# PowerSupply.net
KiCad netlist of a schematic drawn in EAGLE
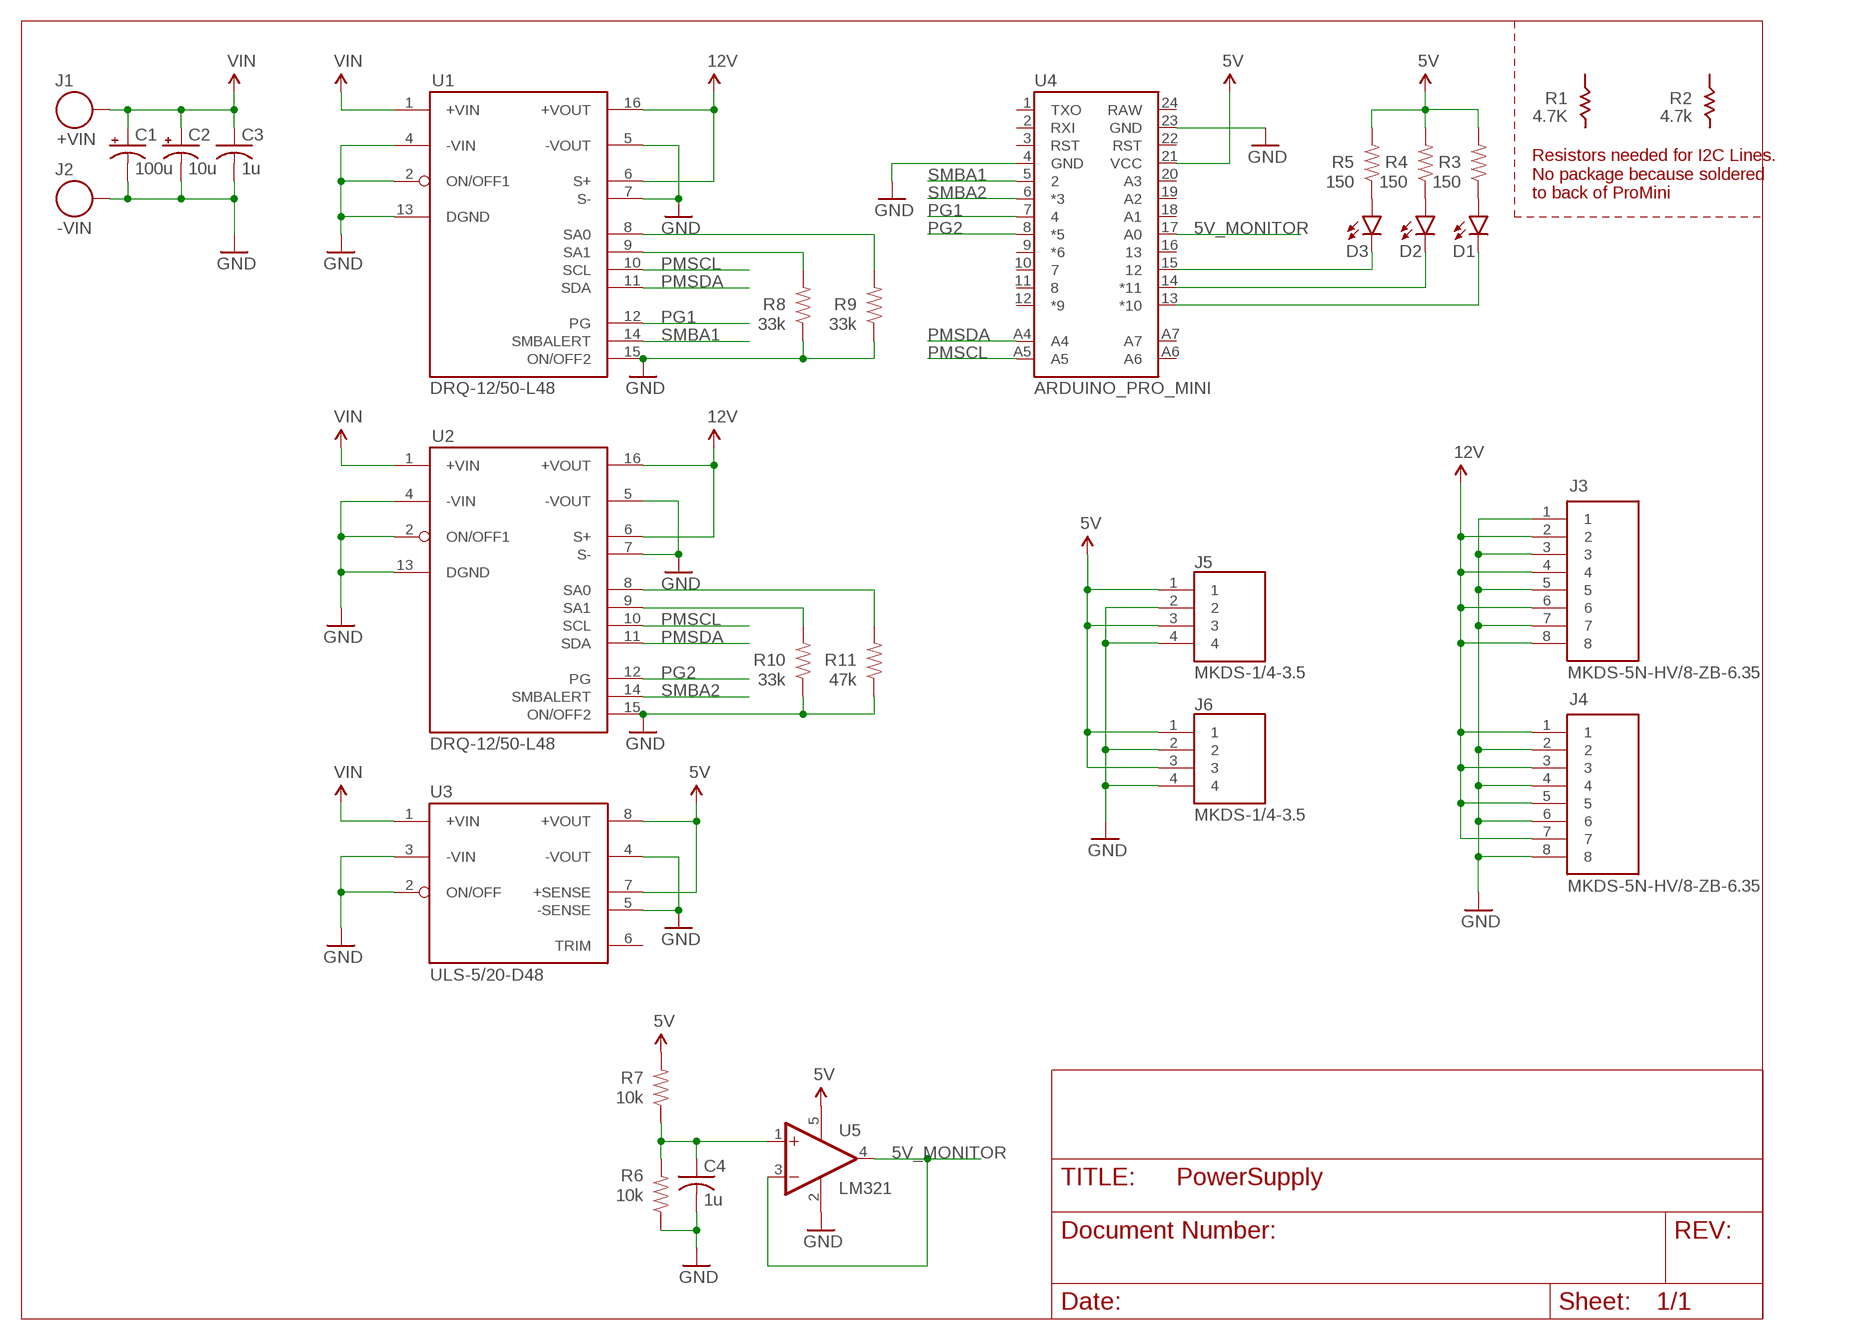
[diagram p0: schematic, sheet 1]

(export (version "E")
  (design (tool "Eeschema 10.0.6"))
  (components
    (comp (ref "C1")
      (value "100u")
      (footprint "eagle-import:PANASONIC_E")
      (libsource (lib "eagle-import") (part "CPOL-USE"))
    )
    (comp (ref "C2")
      (value "10u")
      (footprint "eagle-import:PANASONIC_D")
      (libsource (lib "eagle-import") (part "CPOL-USD"))
    )
    (comp (ref "C3")
      (value "1u")
      (footprint "eagle-import:C0603")
      (libsource (lib "eagle-import") (part "C-USC0603"))
    )
    (comp (ref "C4")
      (value "1u")
      (footprint "eagle-import:C0603")
      (libsource (lib "eagle-import") (part "C-USC0603"))
    )
    (comp (ref "D1")
      (value "LED1206")
      (footprint "eagle-import:LED-1206")
      (libsource (lib "eagle-import") (part "LED1206"))
    )
    (comp (ref "D2")
      (value "LED1206")
      (footprint "eagle-import:LED-1206")
      (libsource (lib "eagle-import") (part "LED1206"))
    )
    (comp (ref "D3")
      (value "LED1206")
      (footprint "eagle-import:LED-1206")
      (libsource (lib "eagle-import") (part "LED1206"))
    )
    (comp (ref "J1")
      (value "+VIN")
      (footprint "eagle-import:10AWG")
      (libsource (lib "eagle-import") (part "SINGLE_PIN"))
    )
    (comp (ref "J2")
      (value "-VIN")
      (footprint "eagle-import:10AWG")
      (libsource (lib "eagle-import") (part "SINGLE_PIN"))
    )
    (comp (ref "J3")
      (value "MKDS-5N-HV/8-ZB-6.35")
      (footprint "eagle-import:1777600")
      (libsource (lib "eagle-import") (part "MKDS-5N-HV/8-ZB-6.35"))
    )
    (comp (ref "J4")
      (value "MKDS-5N-HV/8-ZB-6.35")
      (footprint "eagle-import:1777600")
      (libsource (lib "eagle-import") (part "MKDS-5N-HV/8-ZB-6.35"))
    )
    (comp (ref "J5")
      (value "MKDS-1/4-3.5")
      (footprint "eagle-import:1751264")
      (libsource (lib "eagle-import") (part "MKDS-1/4-3.5"))
    )
    (comp (ref "J6")
      (value "MKDS-1/4-3.5")
      (footprint "eagle-import:1751264")
      (libsource (lib "eagle-import") (part "MKDS-1/4-3.5"))
    )
    (comp (ref "R3")
      (value "150")
      (footprint "eagle-import:0603-RES")
      (libsource (lib "eagle-import") (part "RESISTOR0603-RES"))
    )
    (comp (ref "R4")
      (value "150")
      (footprint "eagle-import:0603-RES")
      (libsource (lib "eagle-import") (part "RESISTOR0603-RES"))
    )
    (comp (ref "R5")
      (value "150")
      (footprint "eagle-import:0603-RES")
      (libsource (lib "eagle-import") (part "RESISTOR0603-RES"))
    )
    (comp (ref "R6")
      (value "10k")
      (footprint "eagle-import:0603-RES")
      (libsource (lib "eagle-import") (part "RESISTOR0603-RES"))
    )
    (comp (ref "R7")
      (value "10k")
      (footprint "eagle-import:0603-RES")
      (libsource (lib "eagle-import") (part "RESISTOR0603-RES"))
    )
    (comp (ref "R8")
      (value "33k")
      (footprint "eagle-import:0603-RES")
      (libsource (lib "eagle-import") (part "RESISTOR0603-RES"))
    )
    (comp (ref "R9")
      (value "33k")
      (footprint "eagle-import:0603-RES")
      (libsource (lib "eagle-import") (part "RESISTOR0603-RES"))
    )
    (comp (ref "R10")
      (value "33k")
      (footprint "eagle-import:0603-RES")
      (libsource (lib "eagle-import") (part "RESISTOR0603-RES"))
    )
    (comp (ref "R11")
      (value "47k")
      (footprint "eagle-import:0603-RES")
      (libsource (lib "eagle-import") (part "RESISTOR0603-RES"))
    )
    (comp (ref "U1")
      (value "DRQ-12/50-L48")
      (footprint "eagle-import:ABC(PMBUS)")
      (libsource (lib "eagle-import") (part "DRQ-12/50-L48"))
    )
    (comp (ref "U2")
      (value "DRQ-12/50-L48")
      (footprint "eagle-import:ABC(PMBUS)")
      (libsource (lib "eagle-import") (part "DRQ-12/50-L48"))
    )
    (comp (ref "U3")
      (value "ULS-5/20-D48")
      (footprint "eagle-import:1_16_BRICK_THROUGH_HOLE")
      (libsource (lib "eagle-import") (part "ULS-5/20-D48"))
    )
    (comp (ref "U4")
      (value "ARDUINO_PRO_MINI")
      (footprint "eagle-import:ARDUINO_PRO_MINI")
      (libsource (lib "eagle-import") (part "ARDUINO_PRO_MINI"))
    )
    (comp (ref "U5")
      (value "LM321")
      (footprint "eagle-import:SOT23-5")
      (libsource (lib "eagle-import") (part "LM321?MF"))
    )
  )
  (nets
    (net (code "1") (name "/5V_MONITOR") (class "Default")
      (node (ref "U4") (pin "17") (pinfunction "A0_17") (pintype "bidirectional"))
      (node (ref "U5") (pin "3") (pinfunction "-IN_3") (pintype "input"))
      (node (ref "U5") (pin "4") (pinfunction "OUT_4") (pintype "output"))
    )
    (net (code "2") (name "/PG1") (class "Default")
      (node (ref "U1") (pin "12") (pinfunction "PG_12") (pintype "bidirectional"))
      (node (ref "U4") (pin "7") (pinfunction "4_7") (pintype "bidirectional"))
    )
    (net (code "3") (name "/PG2") (class "Default")
      (node (ref "U2") (pin "12") (pinfunction "PG_12") (pintype "bidirectional"))
      (node (ref "U4") (pin "8") (pinfunction "*5_8") (pintype "bidirectional"))
    )
    (net (code "4") (name "/PMSCL") (class "Default")
      (node (ref "U1") (pin "10") (pinfunction "SCL_10") (pintype "bidirectional"))
      (node (ref "U2") (pin "10") (pinfunction "SCL_10") (pintype "bidirectional"))
      (node (ref "U4") (pin "A5") (pinfunction "A5_A5") (pintype "bidirectional"))
    )
    (net (code "5") (name "/PMSDA") (class "Default")
      (node (ref "U1") (pin "11") (pinfunction "SDA_11") (pintype "bidirectional"))
      (node (ref "U2") (pin "11") (pinfunction "SDA_11") (pintype "bidirectional"))
      (node (ref "U4") (pin "A4") (pinfunction "A4_A4") (pintype "bidirectional"))
    )
    (net (code "6") (name "/SMBA1") (class "Default")
      (node (ref "U1") (pin "14") (pinfunction "SMBALERT_14") (pintype "bidirectional"))
      (node (ref "U4") (pin "5") (pinfunction "2_5") (pintype "bidirectional"))
    )
    (net (code "7") (name "/SMBA2") (class "Default")
      (node (ref "U2") (pin "14") (pinfunction "SMBALERT_14") (pintype "bidirectional"))
      (node (ref "U4") (pin "6") (pinfunction "*3_6") (pintype "bidirectional"))
    )
    (net (code "8") (name "5V") (class "Default")
      (node (ref "J5") (pin "1") (pinfunction "1_1") (pintype "bidirectional"))
      (node (ref "J5") (pin "3") (pinfunction "3_3") (pintype "bidirectional"))
      (node (ref "J6") (pin "1") (pinfunction "1_1") (pintype "bidirectional"))
      (node (ref "J6") (pin "3") (pinfunction "3_3") (pintype "bidirectional"))
      (node (ref "R3") (pin "2") (pinfunction "2_2") (pintype "passive"))
      (node (ref "R4") (pin "2") (pinfunction "2_2") (pintype "passive"))
      (node (ref "R5") (pin "2") (pinfunction "2_2") (pintype "passive"))
      (node (ref "R7") (pin "2") (pinfunction "2_2") (pintype "passive"))
      (node (ref "U3") (pin "7") (pinfunction "+SENSE_7") (pintype "bidirectional"))
      (node (ref "U3") (pin "8") (pinfunction "+VOUT_8") (pintype "bidirectional"))
      (node (ref "U4") (pin "21") (pinfunction "VCC_21") (pintype "bidirectional"))
      (node (ref "U5") (pin "5") (pinfunction "V+_5") (pintype "power_in"))
    )
    (net (code "9") (name "12V") (class "Default")
      (node (ref "J3") (pin "2") (pinfunction "2_2") (pintype "bidirectional"))
      (node (ref "J3") (pin "4") (pinfunction "4_4") (pintype "bidirectional"))
      (node (ref "J3") (pin "6") (pinfunction "6_6") (pintype "bidirectional"))
      (node (ref "J3") (pin "8") (pinfunction "8_8") (pintype "bidirectional"))
      (node (ref "J4") (pin "1") (pinfunction "1_1") (pintype "bidirectional"))
      (node (ref "J4") (pin "3") (pinfunction "3_3") (pintype "bidirectional"))
      (node (ref "J4") (pin "5") (pinfunction "5_5") (pintype "bidirectional"))
      (node (ref "J4") (pin "7") (pinfunction "7_7") (pintype "bidirectional"))
      (node (ref "U1") (pin "16") (pinfunction "+VOUT_16") (pintype "bidirectional"))
      (node (ref "U1") (pin "6") (pinfunction "S+_6") (pintype "bidirectional"))
      (node (ref "U2") (pin "16") (pinfunction "+VOUT_16") (pintype "bidirectional"))
      (node (ref "U2") (pin "6") (pinfunction "S+_6") (pintype "bidirectional"))
    )
    (net (code "10") (name "GND") (class "Default")
      (node (ref "C1") (pin "-") (pinfunction "-_-") (pintype "passive"))
      (node (ref "C2") (pin "-") (pinfunction "-_-") (pintype "passive"))
      (node (ref "C3") (pin "2") (pinfunction "2_2") (pintype "passive"))
      (node (ref "C4") (pin "2") (pinfunction "2_2") (pintype "passive"))
      (node (ref "J2") (pin "P$1") (pinfunction "P$1_P$1") (pintype "bidirectional"))
      (node (ref "J3") (pin "1") (pinfunction "1_1") (pintype "bidirectional"))
      (node (ref "J3") (pin "3") (pinfunction "3_3") (pintype "bidirectional"))
      (node (ref "J3") (pin "5") (pinfunction "5_5") (pintype "bidirectional"))
      (node (ref "J3") (pin "7") (pinfunction "7_7") (pintype "bidirectional"))
      (node (ref "J4") (pin "2") (pinfunction "2_2") (pintype "bidirectional"))
      (node (ref "J4") (pin "4") (pinfunction "4_4") (pintype "bidirectional"))
      (node (ref "J4") (pin "6") (pinfunction "6_6") (pintype "bidirectional"))
      (node (ref "J4") (pin "8") (pinfunction "8_8") (pintype "bidirectional"))
      (node (ref "J5") (pin "2") (pinfunction "2_2") (pintype "bidirectional"))
      (node (ref "J5") (pin "4") (pinfunction "4_4") (pintype "bidirectional"))
      (node (ref "J6") (pin "2") (pinfunction "2_2") (pintype "bidirectional"))
      (node (ref "J6") (pin "4") (pinfunction "4_4") (pintype "bidirectional"))
      (node (ref "R10") (pin "1") (pinfunction "1_1") (pintype "passive"))
      (node (ref "R11") (pin "1") (pinfunction "1_1") (pintype "passive"))
      (node (ref "R6") (pin "1") (pinfunction "1_1") (pintype "passive"))
      (node (ref "R8") (pin "1") (pinfunction "1_1") (pintype "passive"))
      (node (ref "R9") (pin "1") (pinfunction "1_1") (pintype "passive"))
      (node (ref "U1") (pin "13") (pinfunction "DGND_13") (pintype "bidirectional"))
      (node (ref "U1") (pin "15") (pinfunction "ON/OFF2_15") (pintype "bidirectional"))
      (node (ref "U1") (pin "2") (pinfunction "ON/OFF1_2") (pintype "bidirectional"))
      (node (ref "U1") (pin "4") (pinfunction "-VIN_4") (pintype "bidirectional"))
      (node (ref "U1") (pin "5") (pinfunction "-VOUT_5") (pintype "bidirectional"))
      (node (ref "U1") (pin "7") (pinfunction "S-_7") (pintype "bidirectional"))
      (node (ref "U2") (pin "13") (pinfunction "DGND_13") (pintype "bidirectional"))
      (node (ref "U2") (pin "15") (pinfunction "ON/OFF2_15") (pintype "bidirectional"))
      (node (ref "U2") (pin "2") (pinfunction "ON/OFF1_2") (pintype "bidirectional"))
      (node (ref "U2") (pin "4") (pinfunction "-VIN_4") (pintype "bidirectional"))
      (node (ref "U2") (pin "5") (pinfunction "-VOUT_5") (pintype "bidirectional"))
      (node (ref "U2") (pin "7") (pinfunction "S-_7") (pintype "bidirectional"))
      (node (ref "U3") (pin "2") (pinfunction "ON/OFF_2") (pintype "bidirectional"))
      (node (ref "U3") (pin "3") (pinfunction "-VIN_3") (pintype "bidirectional"))
      (node (ref "U3") (pin "4") (pinfunction "-VOUT_4") (pintype "bidirectional"))
      (node (ref "U3") (pin "5") (pinfunction "-SENSE_5") (pintype "bidirectional"))
      (node (ref "U4") (pin "23") (pinfunction "GND_23") (pintype "bidirectional"))
      (node (ref "U4") (pin "4") (pinfunction "GND_4") (pintype "bidirectional"))
      (node (ref "U5") (pin "2") (pinfunction "V-_2") (pintype "power_in"))
    )
    (net (code "11") (name "Net-(D1-PadA)") (class "Default")
      (node (ref "D1") (pin "A") (pinfunction "A_A") (pintype "passive"))
      (node (ref "R3") (pin "1") (pinfunction "1_1") (pintype "passive"))
    )
    (net (code "12") (name "Net-(D2-PadA)") (class "Default")
      (node (ref "D2") (pin "A") (pinfunction "A_A") (pintype "passive"))
      (node (ref "R4") (pin "1") (pinfunction "1_1") (pintype "passive"))
    )
    (net (code "13") (name "Net-(D3-PadA)") (class "Default")
      (node (ref "D3") (pin "A") (pinfunction "A_A") (pintype "passive"))
      (node (ref "R5") (pin "1") (pinfunction "1_1") (pintype "passive"))
    )
    (net (code "14") (name "Net-(U1-SA0)") (class "Default")
      (node (ref "R9") (pin "2") (pinfunction "2_2") (pintype "passive"))
      (node (ref "U1") (pin "8") (pinfunction "SA0_8") (pintype "bidirectional"))
    )
    (net (code "15") (name "Net-(U1-SA1)") (class "Default")
      (node (ref "R8") (pin "2") (pinfunction "2_2") (pintype "passive"))
      (node (ref "U1") (pin "9") (pinfunction "SA1_9") (pintype "bidirectional"))
    )
    (net (code "16") (name "Net-(U2-SA0)") (class "Default")
      (node (ref "R11") (pin "2") (pinfunction "2_2") (pintype "passive"))
      (node (ref "U2") (pin "8") (pinfunction "SA0_8") (pintype "bidirectional"))
    )
    (net (code "17") (name "Net-(U2-SA1)") (class "Default")
      (node (ref "R10") (pin "2") (pinfunction "2_2") (pintype "passive"))
      (node (ref "U2") (pin "9") (pinfunction "SA1_9") (pintype "bidirectional"))
    )
    (net (code "18") (name "Net-(U4-*10)") (class "Default")
      (node (ref "D1") (pin "C") (pinfunction "C_C") (pintype "passive"))
      (node (ref "U4") (pin "13") (pinfunction "*10_13") (pintype "bidirectional"))
    )
    (net (code "19") (name "Net-(U4-*11)") (class "Default")
      (node (ref "D2") (pin "C") (pinfunction "C_C") (pintype "passive"))
      (node (ref "U4") (pin "14") (pinfunction "*11_14") (pintype "bidirectional"))
    )
    (net (code "20") (name "Net-(U4-12)") (class "Default")
      (node (ref "D3") (pin "C") (pinfunction "C_C") (pintype "passive"))
      (node (ref "U4") (pin "15") (pinfunction "12_15") (pintype "bidirectional"))
    )
    (net (code "21") (name "Net-(U5-+IN)") (class "Default")
      (node (ref "C4") (pin "1") (pinfunction "1_1") (pintype "passive"))
      (node (ref "R6") (pin "2") (pinfunction "2_2") (pintype "passive"))
      (node (ref "R7") (pin "1") (pinfunction "1_1") (pintype "passive"))
      (node (ref "U5") (pin "1") (pinfunction "+IN_1") (pintype "input"))
    )
    (net (code "22") (name "VIN") (class "Default")
      (node (ref "C1") (pin "+") (pinfunction "+_+") (pintype "passive"))
      (node (ref "C2") (pin "+") (pinfunction "+_+") (pintype "passive"))
      (node (ref "C3") (pin "1") (pinfunction "1_1") (pintype "passive"))
      (node (ref "J1") (pin "P$1") (pinfunction "P$1_P$1") (pintype "bidirectional"))
      (node (ref "U1") (pin "1") (pinfunction "+VIN_1") (pintype "bidirectional"))
      (node (ref "U2") (pin "1") (pinfunction "+VIN_1") (pintype "bidirectional"))
      (node (ref "U3") (pin "1") (pinfunction "+VIN_1") (pintype "bidirectional"))
    )
    (net (code "23") (name "unconnected-(U3-TRIM-Pad6)") (class "Default")
      (node (ref "U3") (pin "6") (pinfunction "TRIM_6") (pintype "bidirectional"))
    )
    (net (code "24") (name "unconnected-(U4-*6-Pad9)") (class "Default")
      (node (ref "U4") (pin "9") (pinfunction "*6_9") (pintype "bidirectional"))
    )
    (net (code "25") (name "unconnected-(U4-*9-Pad12)") (class "Default")
      (node (ref "U4") (pin "12") (pinfunction "*9_12") (pintype "bidirectional"))
    )
    (net (code "26") (name "unconnected-(U4-7-Pad10)") (class "Default")
      (node (ref "U4") (pin "10") (pinfunction "7_10") (pintype "bidirectional"))
    )
    (net (code "27") (name "unconnected-(U4-8-Pad11)") (class "Default")
      (node (ref "U4") (pin "11") (pinfunction "8_11") (pintype "bidirectional"))
    )
    (net (code "28") (name "unconnected-(U4-13-Pad16)") (class "Default")
      (node (ref "U4") (pin "16") (pinfunction "13_16") (pintype "bidirectional"))
    )
    (net (code "29") (name "unconnected-(U4-A1-Pad18)") (class "Default")
      (node (ref "U4") (pin "18") (pinfunction "A1_18") (pintype "bidirectional"))
    )
    (net (code "30") (name "unconnected-(U4-A2-Pad19)") (class "Default")
      (node (ref "U4") (pin "19") (pinfunction "A2_19") (pintype "bidirectional"))
    )
    (net (code "31") (name "unconnected-(U4-A3-Pad20)") (class "Default")
      (node (ref "U4") (pin "20") (pinfunction "A3_20") (pintype "bidirectional"))
    )
    (net (code "32") (name "unconnected-(U4-PadA6)") (class "Default")
      (node (ref "U4") (pin "A6") (pinfunction "A6_A6") (pintype "bidirectional"))
    )
    (net (code "33") (name "unconnected-(U4-PadA7)") (class "Default")
      (node (ref "U4") (pin "A7") (pinfunction "A7_A7") (pintype "bidirectional"))
    )
    (net (code "34") (name "unconnected-(U4-RAW-Pad24)") (class "Default")
      (node (ref "U4") (pin "24") (pinfunction "RAW_24") (pintype "bidirectional"))
    )
    (net (code "35") (name "unconnected-(U4-RST-Pad3)") (class "Default")
      (node (ref "U4") (pin "3") (pinfunction "RST_3") (pintype "bidirectional"))
    )
    (net (code "36") (name "unconnected-(U4-RST-Pad22)") (class "Default")
      (node (ref "U4") (pin "22") (pinfunction "RST_22") (pintype "bidirectional"))
    )
    (net (code "37") (name "unconnected-(U4-RXI-Pad2)") (class "Default")
      (node (ref "U4") (pin "2") (pinfunction "RXI_2") (pintype "bidirectional"))
    )
    (net (code "38") (name "unconnected-(U4-TXO-Pad1)") (class "Default")
      (node (ref "U4") (pin "1") (pinfunction "TXO_1") (pintype "bidirectional"))
    )
  )
)
